# 7_Airframe-Sensors.net
KiCad netlist of a schematic drawn in Altium Designer
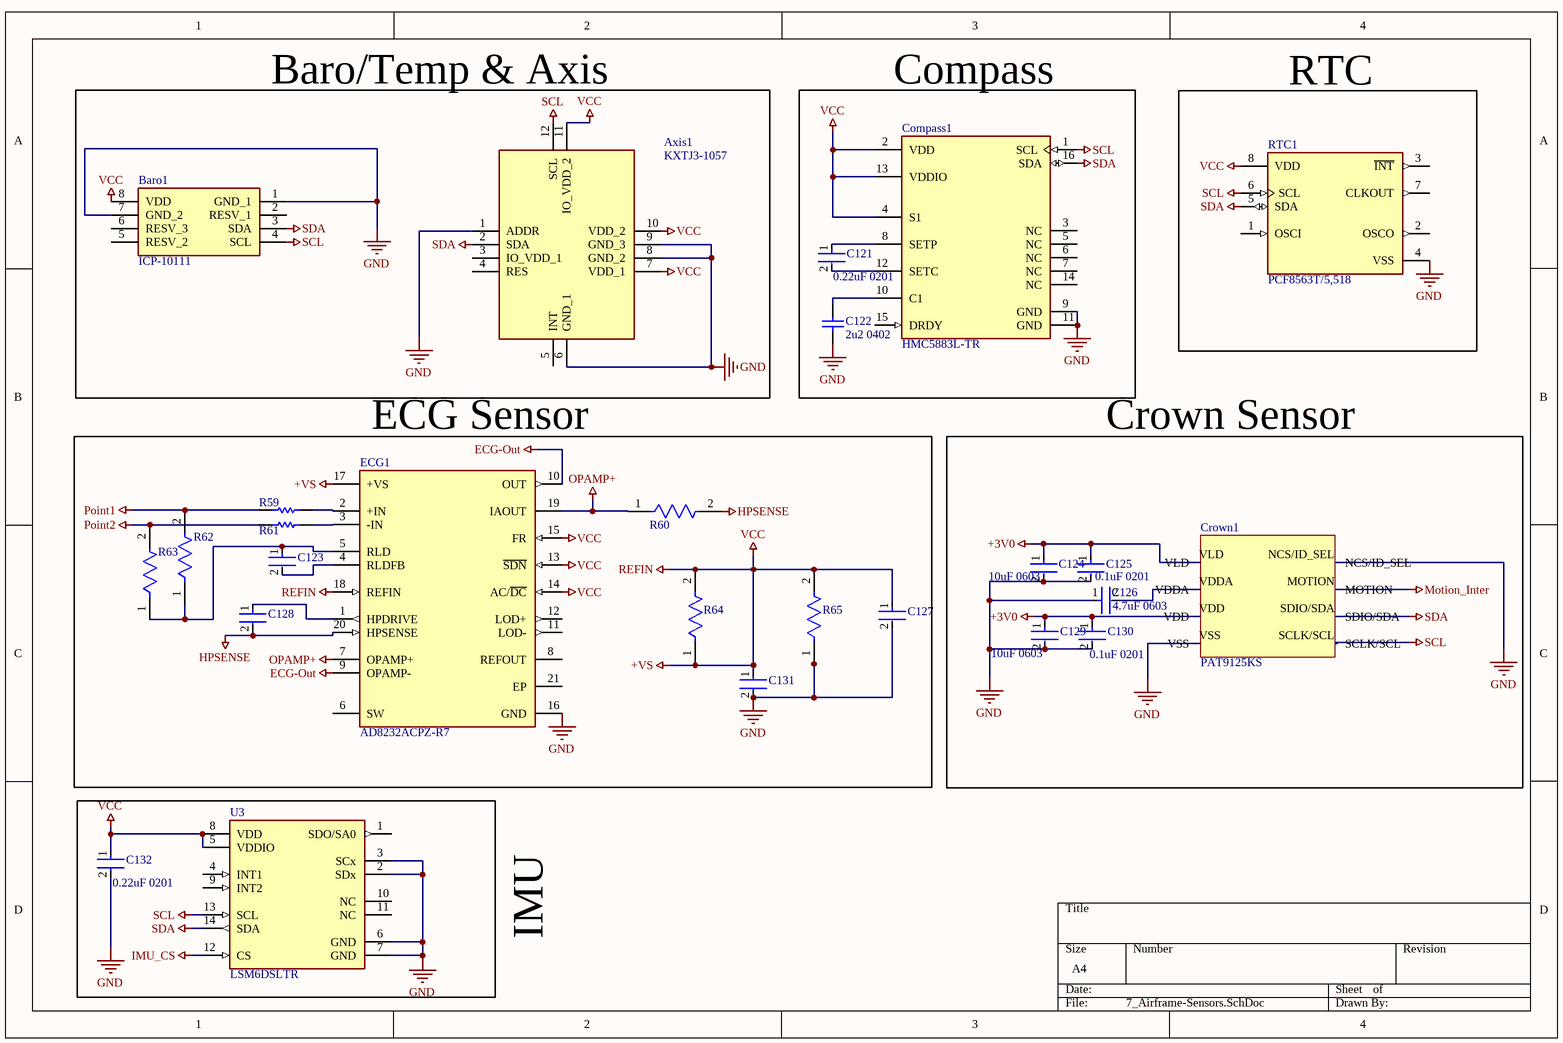
[diagram p0: 7_Airframe-Sensors.SchDoc]

(export (version "E")
  (design (tool "Eeschema 10.0.6"))
  (components
    (comp (ref "Axis1")
      (value "KXTJ3-1057")
      (footprint "SamacSys:2X2X0.9MMLGA")
      (description "Accelerometer")
      (fields (field (name "MOUSER PART NUMBER") "912-KXTJ3-1057"))
      (libsource (lib "*") (part "KXTJ3-1057"))
    )
    (comp (ref "Baro1")
      (value "ICP-10111")
      (footprint "SamacSys:ICP10111")
      (description "Undefined or Miscellaneous")
      (fields (field (name "MOUSER PART NUMBER") "410-ICP-10111"))
      (libsource (lib "*") (part "ICP-10111"))
    )
    (comp (ref "C121")
      (value "0.22uF 0201")
      (footprint "FP-C0603-030-0_03-IPC_C")
      (description "Multilayer Ceramic Capacitors 220nF ±10% 6.3V X6S SMD 0201")
      (fields (field (name "TOLERANCE") "10%"))
      (libsource (lib "Altium Content Vault") (part "02cd4be3c70576c341d710602a673aa"))
    )
    (comp (ref "C122")
      (value "2u2 0402")
      (footprint "CAPC1005X55X25ML5T10")
      (description "Chip Capacitor, 1 nF, +/- 10%, 50 V, -55 to 125 degC, 0402 (1005 Metric), RoHS, Tape and Reel")
      (fields (field (name "TOLERANCE") "10%"))
      (libsource (lib "Altium Content Vault") (part "CAP-NP-2"))
    )
    (comp (ref "C123")
      (value "GRM1555C1H102JA01D")
      (footprint "FP-GRM155-0_05-IPC_B")
      (description "Chip Multilayer Ceramic Capacitors for General Purpose, 0402, 1000pF, C0G, 30ppm/°C, 5%, 50V")
      (fields (field (name "TOLERANCE") "5%") (field (name "VOLTAGE") "50V"))
      (libsource (lib "Altium Content Vault") (part "02cd4be3c70576c341d710602a673aa"))
    )
    (comp (ref "C124")
      (value "10uF 0603")
      (footprint "FP-GRM188-0_2-IPC_C")
      (description "Chip Multilayer Ceramic Capacitors for General Purpose, 0603, 22uF, X5R, 15%, 20%, 10V")
      (fields (field (name "TOLERANCE") "20%"))
      (libsource (lib "Altium Content Vault") (part "11868f565c42a9108669ba33697ecf6"))
    )
    (comp (ref "C125")
      (value "0.1uF 0201")
      (footprint "FP-C0603-030-0_03-IPC_C")
      (description "Multilayer Ceramic Capacitors 220nF ±10% 6.3V X6S SMD 0201")
      (fields (field (name "TOLERANCE") "10%"))
      (libsource (lib "Altium Content Vault") (part "02cd4be3c70576c341d710602a673aa"))
    )
    (comp (ref "C126")
      (value "4.7uF 0603")
      (footprint "FP-GRM188-0_2-IPC_C")
      (description "Chip Multilayer Ceramic Capacitors for General Purpose, 0603, 22uF, X5R, 15%, 20%, 10V")
      (fields (field (name "TOLERANCE") "20%"))
      (libsource (lib "Altium Content Vault") (part "11868f565c42a9108669ba33697ecf6"))
    )
    (comp (ref "C127")
      (value "C0402C104K8PACTU")
      (footprint "FP-C0402-BB-MFG")
      (description "CAP CER 0.1UF 10V X5R 0402")
      (fields (field (name "MANUFACTURER") "Kemet") (field (name "TOLERANCE") "0.1"))
      (libsource (lib "Altium Content Vault") (part "b4654b650e69147ec39a6b967a45e02"))
    )
    (comp (ref "C128")
      (value "GRM155R71C224KA12D")
      (footprint "FP-GRM155-0_05-IPC_C")
      (description "Chip Multilayer Ceramic Capacitors for General Purpose, 0402, 0.22uF, X7R, 15%, 10%, 16V")
      (fields (field (name "VOLTAGE") "16V") (field (name "TOLERANCE") "10%"))
      (libsource (lib "Altium Content Vault") (part "02cd4be3c70576c341d710602a673aa"))
    )
    (comp (ref "C129")
      (value "10uF 0603")
      (footprint "FP-GRM188-0_2-IPC_C")
      (description "Chip Multilayer Ceramic Capacitors for General Purpose, 0603, 22uF, X5R, 15%, 20%, 10V")
      (fields (field (name "TOLERANCE") "20%"))
      (libsource (lib "Altium Content Vault") (part "11868f565c42a9108669ba33697ecf6"))
    )
    (comp (ref "C130")
      (value "0.1uF 0201")
      (footprint "FP-C0603-030-0_03-IPC_C")
      (description "Multilayer Ceramic Capacitors 220nF ±10% 6.3V X6S SMD 0201")
      (fields (field (name "TOLERANCE") "10%"))
      (libsource (lib "Altium Content Vault") (part "02cd4be3c70576c341d710602a673aa"))
    )
    (comp (ref "C131")
      (value "C0402C104K8PACTU")
      (footprint "FP-C0402-BB-MFG")
      (description "CAP CER 0.1UF 10V X5R 0402")
      (fields (field (name "MANUFACTURER") "Kemet") (field (name "TOLERANCE") "0.1"))
      (libsource (lib "Altium Content Vault") (part "b4654b650e69147ec39a6b967a45e02"))
    )
    (comp (ref "C132")
      (value "0.22uF 0201")
      (footprint "FP-C0603-030-0_03-IPC_C")
      (description "Multilayer Ceramic Capacitors 220nF ±10% 6.3V X6S SMD 0201")
      (fields (field (name "TOLERANCE") "10%"))
      (libsource (lib "Altium Content Vault") (part "02cd4be3c70576c341d710602a673aa"))
    )
    (comp (ref "Compass1")
      (value "HMC5883L-TR")
      (footprint "FP-HMC5883L-TR-MFG")
      (description "SENSOR MR I2C 16LCC")
      (libsource (lib "Altium Content Vault") (part "8521342e0b275d82ce322def6be45f0"))
    )
    (comp (ref "Crown1")
      (value "PAT9125KS")
      (footprint "PAT9125KS-Footprint-1")
      (libsource (lib "Projects") (part "PAT9125KS-Symbol-1"))
    )
    (comp (ref "ECG1")
      (value "AD8232ACPZ-R7")
      (footprint "FP-CP-20-8-IPC_C")
      (description "IC ECG FRONT END 20LFCSP")
      (libsource (lib "Altium Content Vault") (part "1c637333606c892ebbd82e67949bb2a"))
    )
    (comp (ref "R59")
      (value "RC0402FR-07180KL")
      (footprint "RESC1005X40X25ML05T10")
      (description "Chip Resistor, 180 KOhm, +/- 1%, 62.5 mW, -55 to 155 degC, 0402 (1005 Metric), RoHS, Tape and Reel")
      (fields (field (name "TOLERANCE") "1%") (field (name "MANUFACTURER") "Basic Passives"))
      (libsource (lib "Altium Content Vault") (part "RES-2"))
    )
    (comp (ref "R60")
      (value "CR0402-JW-105GLF")
      (footprint "FP-CR0402-MFG")
      (description "Thick Film Chip Resistors 0402 1MΩ 0.0625W 5% 200ppm/°C")
      (fields (field (name "TOLERANCE") "5%"))
      (libsource (lib "Altium Content Vault") (part "1029c3af85768c4190bb7ad29bc67b5"))
    )
    (comp (ref "R61")
      (value "RC0402FR-07180KL")
      (footprint "RESC1005X40X25ML05T10")
      (description "Chip Resistor, 180 KOhm, +/- 1%, 62.5 mW, -55 to 155 degC, 0402 (1005 Metric), RoHS, Tape and Reel")
      (fields (field (name "TOLERANCE") "1%") (field (name "MANUFACTURER") "Basic Passives"))
      (libsource (lib "Altium Content Vault") (part "RES-2"))
    )
    (comp (ref "R62")
      (value "CR0402-JW-105GLF")
      (footprint "FP-CR0402-MFG")
      (description "Thick Film Chip Resistors 0402 1MΩ 0.0625W 5% 200ppm/°C")
      (fields (field (name "TOLERANCE") "5%"))
      (libsource (lib "Altium Content Vault") (part "1029c3af85768c4190bb7ad29bc67b5"))
    )
    (comp (ref "R63")
      (value "CR0402-JW-105GLF")
      (footprint "FP-CR0402-MFG")
      (description "Thick Film Chip Resistors 0402 1MΩ 0.0625W 5% 200ppm/°C")
      (fields (field (name "TOLERANCE") "5%"))
      (libsource (lib "Altium Content Vault") (part "1029c3af85768c4190bb7ad29bc67b5"))
    )
    (comp (ref "R64")
      (value "CR0402-JW-105GLF")
      (footprint "FP-CR0402-MFG")
      (description "Thick Film Chip Resistors 0402 1MΩ 0.0625W 5% 200ppm/°C")
      (fields (field (name "TOLERANCE") "5%"))
      (libsource (lib "Altium Content Vault") (part "1029c3af85768c4190bb7ad29bc67b5"))
    )
    (comp (ref "R65")
      (value "CR0402-JW-105GLF")
      (footprint "FP-CR0402-MFG")
      (description "Thick Film Chip Resistors 0402 1MΩ 0.0625W 5% 200ppm/°C")
      (fields (field (name "TOLERANCE") "5%"))
      (libsource (lib "Altium Content Vault") (part "1029c3af85768c4190bb7ad29bc67b5"))
    )
    (comp (ref "RTC1")
      (value "PCF8563T/5,518")
      (footprint "FP-SOT96-1-MFG")
      (description "IC RTC CLK/CALENDAR I2C 8-SOIC")
      (fields
        (field (name "OCTOPART") "https://octopart.com/pcf8563t%2F5%2C518-nxp+semiconductors-19647995")
        (field (name "MANUFACTURER") "NXP")
      )
      (libsource (lib "Altium Content Vault") (part "a37bc7bf6ae0839037c7f5583b0f96f"))
    )
    (comp (ref "U3")
      (value "LSM6DSLTR")
      (footprint "FP-LGA-14L-DM00249496-MFG")
      (description "IMU ACCEL/GYRO I2C/SPI 14LGA")
      (fields
        (field (name "MANUFACTURER") "STMicroelectronics")
        (field (name "OCTOPART") "https://octopart.com/lsm6dsltr-stmicroelectronics-66358193")
      )
      (libsource (lib "Altium Content Vault") (part "4e27e7d1829efda5344af1708d65448"))
    )
  )
  (nets
    (net (code "1") (name "+3V0") (class "Default")
      (node (ref "C124") (pin "1") (pinfunction "1_1") (pintype "passive"))
      (node (ref "C125") (pin "1") (pinfunction "1_1") (pintype "passive"))
      (node (ref "C129") (pin "1") (pinfunction "1_1") (pintype "passive"))
      (node (ref "C130") (pin "1") (pinfunction "1_1") (pintype "passive"))
      (node (ref "Crown1") (pin "VDD") (pinfunction "VDD_VDD") (pintype "passive"))
      (node (ref "Crown1") (pin "VLD") (pinfunction "VLD_VLD") (pintype "passive"))
    )
    (net (code "2") (name "+VS") (class "Default")
      (node (ref "Axis1") (pin "10") (pinfunction "VDD_2_10") (pintype "passive"))
      (node (ref "Axis1") (pin "11") (pinfunction "IO_VDD_2_11") (pintype "passive"))
      (node (ref "Axis1") (pin "7") (pinfunction "VDD_1_7") (pintype "passive"))
      (node (ref "Baro1") (pin "8") (pinfunction "VDD_8") (pintype "passive"))
      (node (ref "C127") (pin "1") (pinfunction "1_1") (pintype "passive"))
      (node (ref "C131") (pin "1") (pinfunction "1_1") (pintype "passive"))
      (node (ref "C132") (pin "1") (pinfunction "1_1") (pintype "passive"))
      (node (ref "Compass1") (pin "13") (pinfunction "VDDIO_13") (pintype "power_in"))
      (node (ref "Compass1") (pin "2") (pinfunction "VDD_2") (pintype "power_in"))
      (node (ref "Compass1") (pin "4") (pinfunction "S1_4") (pintype "passive"))
      (node (ref "ECG1") (pin "13") (pinfunction "~{SDN}_13") (pintype "input"))
      (node (ref "ECG1") (pin "14") (pinfunction "AC/~{DC}_14") (pintype "input"))
      (node (ref "ECG1") (pin "15") (pinfunction "FR_15") (pintype "input"))
      (node (ref "ECG1") (pin "17") (pinfunction "+VS_17") (pintype "power_in"))
      (node (ref "ECG1") (pin "18") (pinfunction "REFIN_18") (pintype "input"))
      (node (ref "R64") (pin "1") (pinfunction "1_1") (pintype "passive"))
      (node (ref "R64") (pin "2") (pinfunction "2_2") (pintype "passive"))
      (node (ref "R65") (pin "2") (pinfunction "2_2") (pintype "passive"))
      (node (ref "RTC1") (pin "8") (pinfunction "VDD_8") (pintype "power_in"))
      (node (ref "U3") (pin "5") (pinfunction "VDDIO_5") (pintype "power_in"))
      (node (ref "U3") (pin "8") (pinfunction "VDD_8") (pintype "power_in"))
    )
    (net (code "3") (name "ECG-Out") (class "Default")
      (node (ref "ECG1") (pin "10") (pinfunction "OUT_10") (pintype "output"))
      (node (ref "ECG1") (pin "9") (pinfunction "OPAMP-_9") (pintype "tri_state"))
    )
    (net (code "4") (name "GND") (class "Default")
      (node (ref "Axis1") (pin "1") (pinfunction "ADDR_1") (pintype "passive"))
      (node (ref "Axis1") (pin "6") (pinfunction "GND_1_6") (pintype "passive"))
      (node (ref "Axis1") (pin "8") (pinfunction "GND_2_8") (pintype "passive"))
      (node (ref "Axis1") (pin "9") (pinfunction "GND_3_9") (pintype "passive"))
      (node (ref "Baro1") (pin "1") (pinfunction "GND_1_1") (pintype "passive"))
      (node (ref "Baro1") (pin "7") (pinfunction "GND_2_7") (pintype "passive"))
      (node (ref "C122") (pin "2") (pinfunction "2_2") (pintype "passive"))
      (node (ref "C124") (pin "2") (pinfunction "2_2") (pintype "passive"))
      (node (ref "C125") (pin "2") (pinfunction "2_2") (pintype "passive"))
      (node (ref "C126") (pin "1") (pinfunction "1_1") (pintype "passive"))
      (node (ref "C127") (pin "2") (pinfunction "2_2") (pintype "passive"))
      (node (ref "C129") (pin "2") (pinfunction "2_2") (pintype "passive"))
      (node (ref "C130") (pin "2") (pinfunction "2_2") (pintype "passive"))
      (node (ref "C131") (pin "2") (pinfunction "2_2") (pintype "passive"))
      (node (ref "C132") (pin "2") (pinfunction "2_2") (pintype "passive"))
      (node (ref "Compass1") (pin "11") (pinfunction "GND_11") (pintype "power_in"))
      (node (ref "Compass1") (pin "9") (pinfunction "GND_9") (pintype "power_in"))
      (node (ref "Crown1") (pin "NCS/ID_SEL") (pinfunction "NCS/ID_SEL_NCS/ID_SEL") (pintype "passive"))
      (node (ref "Crown1") (pin "VSS") (pinfunction "VSS_VSS") (pintype "passive"))
      (node (ref "ECG1") (pin "16") (pinfunction "GND_16") (pintype "power_in"))
      (node (ref "R65") (pin "1") (pinfunction "1_1") (pintype "passive"))
      (node (ref "RTC1") (pin "4") (pinfunction "VSS_4") (pintype "power_in"))
      (node (ref "U3") (pin "2") (pinfunction "SDx_2") (pintype "passive"))
      (node (ref "U3") (pin "3") (pinfunction "SCx_3") (pintype "passive"))
      (node (ref "U3") (pin "6") (pinfunction "GND_6") (pintype "power_in"))
      (node (ref "U3") (pin "7") (pinfunction "GND_7") (pintype "power_in"))
    )
    (net (code "5") (name "HPSENSE") (class "Default")
      (node (ref "C128") (pin "2") (pinfunction "2_2") (pintype "passive"))
      (node (ref "ECG1") (pin "20") (pinfunction "HPSENSE_20") (pintype "input"))
      (node (ref "R60") (pin "2") (pinfunction "2_2") (pintype "passive"))
    )
    (net (code "6") (name "IMU_CS") (class "Default")
      (node (ref "U3") (pin "12") (pinfunction "CS_12") (pintype "input"))
    )
    (net (code "7") (name "Motion_Inter") (class "Default")
      (node (ref "Crown1") (pin "MOTION") (pinfunction "MOTION_MOTION") (pintype "passive"))
    )
    (net (code "8") (name "Net-(C126-Pad2)") (class "Default")
      (node (ref "C126") (pin "2") (pinfunction "2_2") (pintype "passive"))
      (node (ref "Crown1") (pin "VDDA") (pinfunction "VDDA_VDDA") (pintype "passive"))
    )
    (net (code "9") (name "Net-(Compass1-C1)") (class "Default")
      (node (ref "C122") (pin "1") (pinfunction "1_1") (pintype "passive"))
      (node (ref "Compass1") (pin "10") (pinfunction "C1_10") (pintype "passive"))
    )
    (net (code "10") (name "Net-(Compass1-SETC)") (class "Default")
      (node (ref "C121") (pin "2") (pinfunction "2_2") (pintype "passive"))
      (node (ref "Compass1") (pin "12") (pinfunction "SETC_12") (pintype "passive"))
    )
    (net (code "11") (name "Net-(Compass1-SETP)") (class "Default")
      (node (ref "C121") (pin "1") (pinfunction "1_1") (pintype "passive"))
      (node (ref "Compass1") (pin "8") (pinfunction "SETP_8") (pintype "passive"))
    )
    (net (code "12") (name "Net-(ECG1-+IN)") (class "Default")
      (node (ref "ECG1") (pin "2") (pinfunction "+IN_2") (pintype "tri_state"))
      (node (ref "R59") (pin "2") (pinfunction "2_2") (pintype "passive"))
    )
    (net (code "13") (name "Net-(ECG1--IN)") (class "Default")
      (node (ref "ECG1") (pin "3") (pinfunction "-IN_3") (pintype "tri_state"))
      (node (ref "R61") (pin "2") (pinfunction "2_2") (pintype "passive"))
    )
    (net (code "14") (name "Net-(ECG1-HPDRIVE)") (class "Default")
      (node (ref "C128") (pin "1") (pinfunction "1_1") (pintype "passive"))
      (node (ref "ECG1") (pin "1") (pinfunction "HPDRIVE_1") (pintype "output"))
    )
    (net (code "15") (name "Net-(ECG1-RLD)") (class "Default")
      (node (ref "C123") (pin "1") (pinfunction "1_1") (pintype "passive"))
      (node (ref "ECG1") (pin "5") (pinfunction "RLD_5") (pintype "passive"))
      (node (ref "R62") (pin "1") (pinfunction "1_1") (pintype "passive"))
      (node (ref "R63") (pin "1") (pinfunction "1_1") (pintype "passive"))
    )
    (net (code "16") (name "Net-(ECG1-RLDFB)") (class "Default")
      (node (ref "C123") (pin "2") (pinfunction "2_2") (pintype "passive"))
      (node (ref "ECG1") (pin "4") (pinfunction "RLDFB_4") (pintype "passive"))
    )
    (net (code "17") (name "OPAMP+") (class "Default")
      (node (ref "ECG1") (pin "19") (pinfunction "IAOUT_19") (pintype "passive"))
      (node (ref "ECG1") (pin "7") (pinfunction "OPAMP+_7") (pintype "tri_state"))
      (node (ref "R60") (pin "1") (pinfunction "1_1") (pintype "passive"))
    )
    (net (code "18") (name "Point1") (class "Default")
      (node (ref "R59") (pin "1") (pinfunction "1_1") (pintype "passive"))
      (node (ref "R62") (pin "2") (pinfunction "2_2") (pintype "passive"))
    )
    (net (code "19") (name "Point2") (class "Default")
      (node (ref "R61") (pin "1") (pinfunction "1_1") (pintype "passive"))
      (node (ref "R63") (pin "2") (pinfunction "2_2") (pintype "passive"))
    )
    (net (code "20") (name "SCL") (class "Default")
      (node (ref "Axis1") (pin "12") (pinfunction "SCL_12") (pintype "passive"))
      (node (ref "Baro1") (pin "4") (pinfunction "SCL_4") (pintype "passive"))
      (node (ref "Compass1") (pin "1") (pinfunction "SCL_1") (pintype "input"))
      (node (ref "Crown1") (pin "SCLK/SCL") (pinfunction "SCLK/SCL_SCLK/SCL") (pintype "passive"))
      (node (ref "RTC1") (pin "6") (pinfunction "SCL_6") (pintype "input"))
      (node (ref "U3") (pin "13") (pinfunction "SCL_13") (pintype "input"))
    )
    (net (code "21") (name "SDA") (class "Default")
      (node (ref "Axis1") (pin "2") (pinfunction "SDA_2") (pintype "passive"))
      (node (ref "Baro1") (pin "3") (pinfunction "SDA_3") (pintype "passive"))
      (node (ref "Compass1") (pin "16") (pinfunction "SDA_16") (pintype "bidirectional"))
      (node (ref "Crown1") (pin "SDIO/SDA") (pinfunction "SDIO/SDA_SDIO/SDA") (pintype "passive"))
      (node (ref "RTC1") (pin "5") (pinfunction "SDA_5") (pintype "bidirectional"))
      (node (ref "U3") (pin "14") (pinfunction "SDA_14") (pintype "output"))
    )
    (net (code "22") (name "unconnected-(Axis1-INT-Pad5)") (class "Default")
      (node (ref "Axis1") (pin "5") (pinfunction "INT_5") (pintype "passive"))
    )
    (net (code "23") (name "unconnected-(Axis1-IO_VDD_1-Pad3)") (class "Default")
      (node (ref "Axis1") (pin "3") (pinfunction "IO_VDD_1_3") (pintype "passive"))
    )
    (net (code "24") (name "unconnected-(Axis1-RES-Pad4)") (class "Default")
      (node (ref "Axis1") (pin "4") (pinfunction "RES_4") (pintype "passive"))
    )
    (net (code "25") (name "unconnected-(Baro1-RESV_1-Pad2)") (class "Default")
      (node (ref "Baro1") (pin "2") (pinfunction "RESV_1_2") (pintype "passive"))
    )
    (net (code "26") (name "unconnected-(Baro1-RESV_2-Pad5)") (class "Default")
      (node (ref "Baro1") (pin "5") (pinfunction "RESV_2_5") (pintype "passive"))
    )
    (net (code "27") (name "unconnected-(Baro1-RESV_3-Pad6)") (class "Default")
      (node (ref "Baro1") (pin "6") (pinfunction "RESV_3_6") (pintype "passive"))
    )
    (net (code "28") (name "unconnected-(Compass1-DRDY-Pad15)") (class "Default")
      (node (ref "Compass1") (pin "15") (pinfunction "DRDY_15") (pintype "input"))
    )
    (net (code "29") (name "unconnected-(Compass1-NC-Pad3)") (class "Default")
      (node (ref "Compass1") (pin "3") (pinfunction "NC_3") (pintype "passive"))
    )
    (net (code "30") (name "unconnected-(Compass1-NC-Pad5)") (class "Default")
      (node (ref "Compass1") (pin "5") (pinfunction "NC_5") (pintype "passive"))
    )
    (net (code "31") (name "unconnected-(Compass1-NC-Pad6)") (class "Default")
      (node (ref "Compass1") (pin "6") (pinfunction "NC_6") (pintype "passive"))
    )
    (net (code "32") (name "unconnected-(Compass1-NC-Pad7)") (class "Default")
      (node (ref "Compass1") (pin "7") (pinfunction "NC_7") (pintype "passive"))
    )
    (net (code "33") (name "unconnected-(Compass1-NC-Pad14)") (class "Default")
      (node (ref "Compass1") (pin "14") (pinfunction "NC_14") (pintype "passive"))
    )
    (net (code "34") (name "unconnected-(ECG1-EP-Pad21)") (class "Default")
      (node (ref "ECG1") (pin "21") (pinfunction "EP_21") (pintype "power_in"))
    )
    (net (code "35") (name "unconnected-(ECG1-LOD+-Pad12)") (class "Default")
      (node (ref "ECG1") (pin "12") (pinfunction "LOD+_12") (pintype "output"))
    )
    (net (code "36") (name "unconnected-(ECG1-LOD--Pad11)") (class "Default")
      (node (ref "ECG1") (pin "11") (pinfunction "LOD-_11") (pintype "output"))
    )
    (net (code "37") (name "unconnected-(ECG1-REFOUT-Pad8)") (class "Default")
      (node (ref "ECG1") (pin "8") (pinfunction "REFOUT_8") (pintype "passive"))
    )
    (net (code "38") (name "unconnected-(ECG1-SW-Pad6)") (class "Default")
      (node (ref "ECG1") (pin "6") (pinfunction "SW_6") (pintype "passive"))
    )
    (net (code "39") (name "unconnected-(RTC1-CLKOUT-Pad7)") (class "Default")
      (node (ref "RTC1") (pin "7") (pinfunction "CLKOUT_7") (pintype "output"))
    )
    (net (code "40") (name "unconnected-(RTC1-OSCI-Pad1)") (class "Default")
      (node (ref "RTC1") (pin "1") (pinfunction "OSCI_1") (pintype "input"))
    )
    (net (code "41") (name "unconnected-(RTC1-OSCO-Pad2)") (class "Default")
      (node (ref "RTC1") (pin "2") (pinfunction "OSCO_2") (pintype "output"))
    )
    (net (code "42") (name "unconnected-(RTC1-~{INT}-Pad3)") (class "Default")
      (node (ref "RTC1") (pin "3") (pinfunction "~{INT}_3") (pintype "output"))
    )
    (net (code "43") (name "unconnected-(U3-INT1-Pad4)") (class "Default")
      (node (ref "U3") (pin "4") (pinfunction "INT1_4") (pintype "input"))
    )
    (net (code "44") (name "unconnected-(U3-INT2-Pad9)") (class "Default")
      (node (ref "U3") (pin "9") (pinfunction "INT2_9") (pintype "input"))
    )
    (net (code "45") (name "unconnected-(U3-NC-Pad10)") (class "Default")
      (node (ref "U3") (pin "10") (pinfunction "NC_10") (pintype "passive"))
    )
    (net (code "46") (name "unconnected-(U3-NC-Pad11)") (class "Default")
      (node (ref "U3") (pin "11") (pinfunction "NC_11") (pintype "passive"))
    )
    (net (code "47") (name "unconnected-(U3-SDO{slash}SA0-Pad1)") (class "Default")
      (node (ref "U3") (pin "1") (pinfunction "SDO/SA0_1") (pintype "output"))
    )
  )
)
